# ADCs.net
KiCad netlist of a schematic drawn in Altium Designer
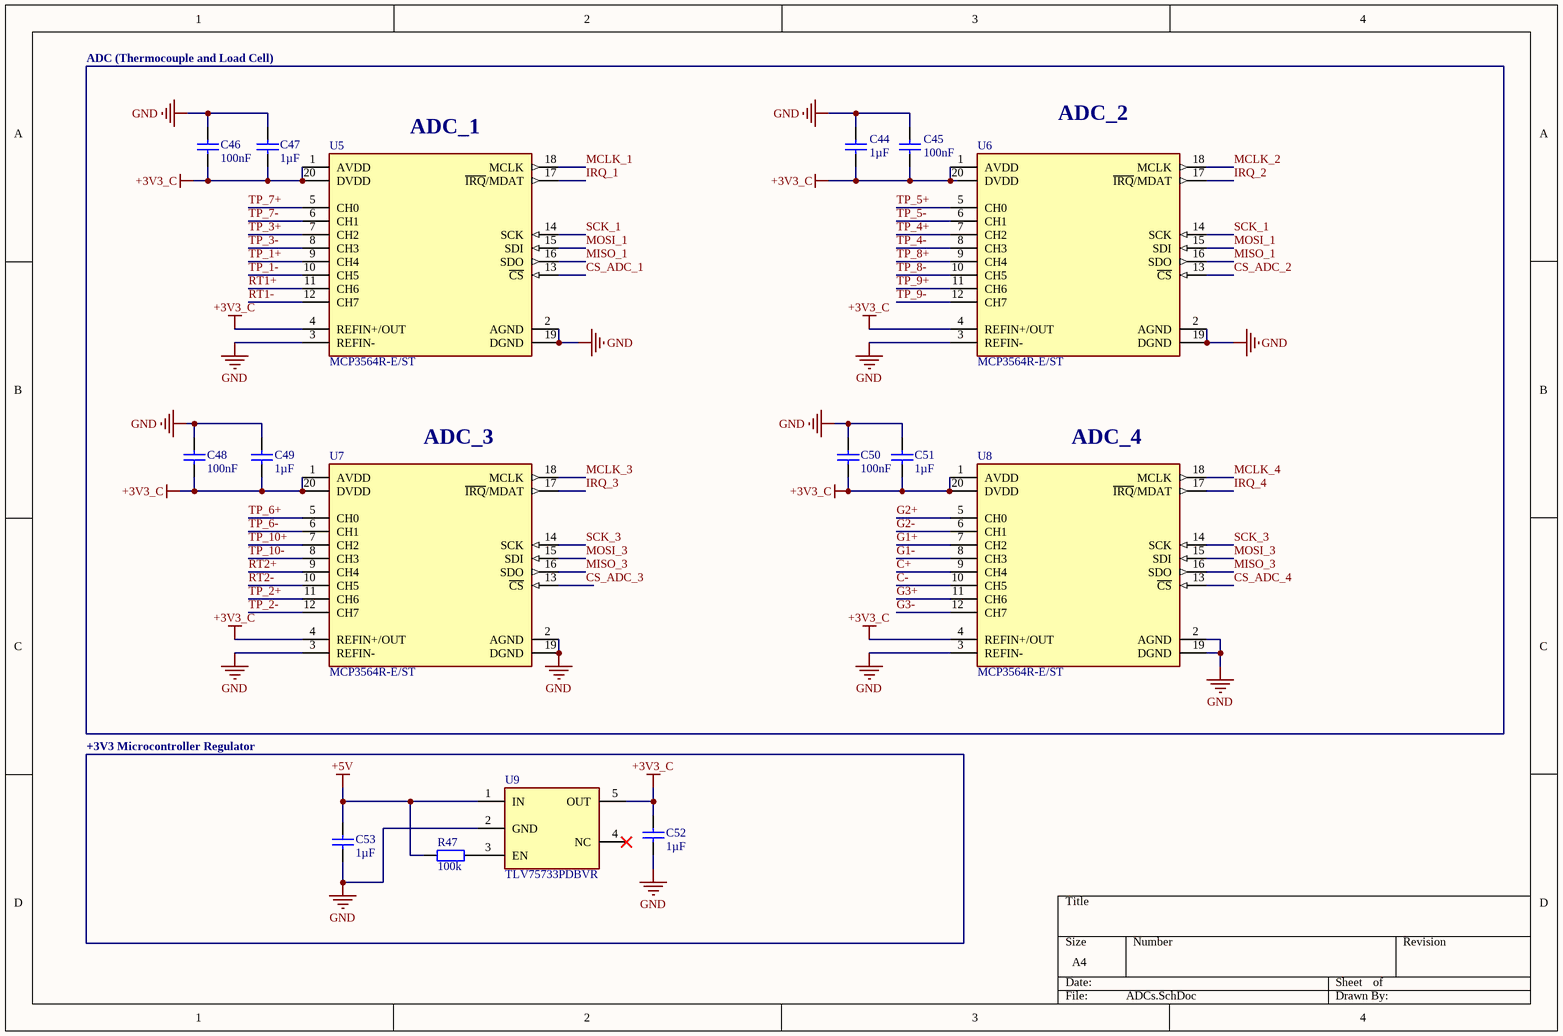
[diagram p0: ADCs.SchDoc]

(export (version "E")
  (design (tool "Eeschema 10.0.6"))
  (components
    (comp (ref "C44")
      (value "1µF")
      (footprint "WCAP-CSGP_0603_L1.6W0.8H0.8_Reflow")
      (description "WCAP-CSGP Multilayer Ceramic Chip Capacitor, General Purpose, size 0603, X7R, 1uF, 16VDC")
      (fields
        (field (name "MANUFACTURER") "Wurth Elektronik")
        (field (name "MANUFACTURER PART NUMBER") "885012206052")
      )
      (libsource (lib "LEEM UPM") (part "885012209047R"))
    )
    (comp (ref "C45")
      (value "100nF")
      (footprint "WCAP-CSGP_0603_L1.6W0.8H0.8_Reflow")
      (description "WCAP-CSGP Multilayer Ceramic Chip Capacitor, General Purpose, size 0603, X7R, 100nF, 25VDC")
      (fields
        (field (name "MANUFACTURER") "Wurth Elektronik")
        (field (name "MANUFACTURER PART NUMBER") "885012206071")
      )
      (libsource (lib "LEEM UPM") (part "885012209047R"))
    )
    (comp (ref "C46")
      (value "100nF")
      (footprint "WCAP-CSGP_0603_L1.6W0.8H0.8_Reflow")
      (description "WCAP-CSGP Multilayer Ceramic Chip Capacitor, General Purpose, size 0603, X7R, 100nF, 25VDC")
      (fields
        (field (name "MANUFACTURER") "Wurth Elektronik")
        (field (name "MANUFACTURER PART NUMBER") "885012206071")
      )
      (libsource (lib "LEEM UPM") (part "885012209047R"))
    )
    (comp (ref "C47")
      (value "1µF")
      (footprint "WCAP-CSGP_0603_L1.6W0.8H0.8_Reflow")
      (description "WCAP-CSGP Multilayer Ceramic Chip Capacitor, General Purpose, size 0603, X7R, 1uF, 16VDC")
      (fields
        (field (name "MANUFACTURER") "Wurth Elektronik")
        (field (name "MANUFACTURER PART NUMBER") "885012206052")
      )
      (libsource (lib "LEEM UPM") (part "885012209047R"))
    )
    (comp (ref "C48")
      (value "100nF")
      (footprint "WCAP-CSGP_0603_L1.6W0.8H0.8_Reflow")
      (description "WCAP-CSGP Multilayer Ceramic Chip Capacitor, General Purpose, size 0603, X7R, 100nF, 25VDC")
      (fields
        (field (name "MANUFACTURER") "Wurth Elektronik")
        (field (name "MANUFACTURER PART NUMBER") "885012206071")
      )
      (libsource (lib "LEEM UPM") (part "885012209047R"))
    )
    (comp (ref "C49")
      (value "1µF")
      (footprint "WCAP-CSGP_0603_L1.6W0.8H0.8_Reflow")
      (description "WCAP-CSGP Multilayer Ceramic Chip Capacitor, General Purpose, size 0603, X7R, 1uF, 16VDC")
      (fields
        (field (name "MANUFACTURER") "Wurth Elektronik")
        (field (name "MANUFACTURER PART NUMBER") "885012206052")
      )
      (libsource (lib "LEEM UPM") (part "885012209047R"))
    )
    (comp (ref "C50")
      (value "100nF")
      (footprint "WCAP-CSGP_0603_L1.6W0.8H0.8_Reflow")
      (description "WCAP-CSGP Multilayer Ceramic Chip Capacitor, General Purpose, size 0603, X7R, 100nF, 25VDC")
      (fields
        (field (name "MANUFACTURER") "Wurth Elektronik")
        (field (name "MANUFACTURER PART NUMBER") "885012206071")
      )
      (libsource (lib "LEEM UPM") (part "885012209047R"))
    )
    (comp (ref "C51")
      (value "1µF")
      (footprint "WCAP-CSGP_0603_L1.6W0.8H0.8_Reflow")
      (description "WCAP-CSGP Multilayer Ceramic Chip Capacitor, General Purpose, size 0603, X7R, 1uF, 16VDC")
      (fields
        (field (name "MANUFACTURER") "Wurth Elektronik")
        (field (name "MANUFACTURER PART NUMBER") "885012206052")
      )
      (libsource (lib "LEEM UPM") (part "885012209047R"))
    )
    (comp (ref "C52")
      (value "1µF")
      (footprint "WCAP-CSGP_0603_L1.6W0.8H0.8_Reflow")
      (description "WCAP-CSGP Multilayer Ceramic Chip Capacitor, General Purpose, size 0603, X7R, 1uF, 16VDC")
      (fields
        (field (name "MANUFACTURER") "Wurth Elektronik")
        (field (name "MANUFACTURER PART NUMBER") "885012206052")
      )
      (libsource (lib "LEEM UPM") (part "885012209047R"))
    )
    (comp (ref "C53")
      (value "1µF")
      (footprint "WCAP-CSGP_0603_L1.6W0.8H0.8_Reflow")
      (description "WCAP-CSGP Multilayer Ceramic Chip Capacitor, General Purpose, size 0603, X7R, 1uF, 16VDC")
      (fields
        (field (name "MANUFACTURER") "Wurth Elektronik")
        (field (name "MANUFACTURER PART NUMBER") "885012206052")
      )
      (libsource (lib "LEEM UPM") (part "885012209047R"))
    )
    (comp (ref "R47")
      (value "100k")
      (footprint "WRIS-RSKS_0603_Reflow")
      (description "WRIS-RSKS Thick Film Resistor, size 0603, 100000Ohm, 100mW")
      (fields
        (field (name "MANUFACTURER PART NUMBER") "560112116004")
        (field (name "MANUFACTURER") "Wurth Elektronik")
      )
      (libsource (lib "LEEM UPM") (part "560112140010"))
    )
    (comp (ref "U5")
      (value "MCP3564R-E/ST")
      (footprint "FP-C04-088-MFG")
      (description "ADC, Delta-Sigma, 24-Bit, 1 Func, 8 Channel, Serial Access, PDSO20")
      (libsource (lib "LEEM UPM") (part "0ac5b573d1d2d90c3815fbc455c1358"))
    )
    (comp (ref "U6")
      (value "MCP3564R-E/ST")
      (footprint "FP-C04-088-MFG")
      (description "ADC, Delta-Sigma, 24-Bit, 1 Func, 8 Channel, Serial Access, PDSO20")
      (libsource (lib "LEEM UPM") (part "0ac5b573d1d2d90c3815fbc455c1358"))
    )
    (comp (ref "U7")
      (value "MCP3564R-E/ST")
      (footprint "FP-C04-088-MFG")
      (description "ADC, Delta-Sigma, 24-Bit, 1 Func, 8 Channel, Serial Access, PDSO20")
      (libsource (lib "LEEM UPM") (part "0ac5b573d1d2d90c3815fbc455c1358"))
    )
    (comp (ref "U8")
      (value "MCP3564R-E/ST")
      (footprint "FP-C04-088-MFG")
      (description "ADC, Delta-Sigma, 24-Bit, 1 Func, 8 Channel, Serial Access, PDSO20")
      (libsource (lib "LEEM UPM") (part "0ac5b573d1d2d90c3815fbc455c1358"))
    )
    (comp (ref "U9")
      (value "TLV75733PDBVR")
      (footprint "SOT95P280X145-5N")
      (description "LDO Voltage Regulators 1A Low-IQ Small-Size Low-Dropout (LDO) Regulator 5-SOT-23 -40 to 125")
      (fields (field (name "MANUFACTURER") "Texas Instruments"))
      (libsource (lib "LEEM UPM") (part "TLV75733PDBVR"))
    )
  )
  (nets
    (net (code "1") (name "+3V3_C") (class "Default")
      (node (ref "C44") (pin "2") (pinfunction "2_2") (pintype "passive"))
      (node (ref "C45") (pin "1") (pinfunction "1_1") (pintype "passive"))
      (node (ref "C46") (pin "2") (pinfunction "2_2") (pintype "passive"))
      (node (ref "C47") (pin "1") (pinfunction "1_1") (pintype "passive"))
      (node (ref "C48") (pin "2") (pinfunction "2_2") (pintype "passive"))
      (node (ref "C49") (pin "1") (pinfunction "1_1") (pintype "passive"))
      (node (ref "C50") (pin "2") (pinfunction "2_2") (pintype "passive"))
      (node (ref "C51") (pin "1") (pinfunction "1_1") (pintype "passive"))
      (node (ref "C52") (pin "2") (pinfunction "2_2") (pintype "passive"))
      (node (ref "U5") (pin "1") (pinfunction "AVDD_1") (pintype "power_in"))
      (node (ref "U5") (pin "20") (pinfunction "DVDD_20") (pintype "power_in"))
      (node (ref "U5") (pin "4") (pinfunction "REFIN+/OUT_4") (pintype "passive"))
      (node (ref "U6") (pin "1") (pinfunction "AVDD_1") (pintype "power_in"))
      (node (ref "U6") (pin "20") (pinfunction "DVDD_20") (pintype "power_in"))
      (node (ref "U6") (pin "4") (pinfunction "REFIN+/OUT_4") (pintype "passive"))
      (node (ref "U7") (pin "1") (pinfunction "AVDD_1") (pintype "power_in"))
      (node (ref "U7") (pin "20") (pinfunction "DVDD_20") (pintype "power_in"))
      (node (ref "U7") (pin "4") (pinfunction "REFIN+/OUT_4") (pintype "passive"))
      (node (ref "U8") (pin "1") (pinfunction "AVDD_1") (pintype "power_in"))
      (node (ref "U8") (pin "20") (pinfunction "DVDD_20") (pintype "power_in"))
      (node (ref "U8") (pin "4") (pinfunction "REFIN+/OUT_4") (pintype "passive"))
      (node (ref "U9") (pin "5") (pinfunction "OUT_5") (pintype "passive"))
    )
    (net (code "2") (name "+5V") (class "Default")
      (node (ref "C53") (pin "2") (pinfunction "2_2") (pintype "passive"))
      (node (ref "R47") (pin "1") (pinfunction "1_1") (pintype "passive"))
      (node (ref "U9") (pin "1") (pinfunction "IN_1") (pintype "power_in"))
    )
    (net (code "3") (name "/C+") (class "Default")
      (node (ref "U8") (pin "9") (pinfunction "CH4_9") (pintype "passive"))
    )
    (net (code "4") (name "/C-") (class "Default")
      (node (ref "U8") (pin "10") (pinfunction "CH5_10") (pintype "passive"))
    )
    (net (code "5") (name "/CS_ADC_1") (class "Default")
      (node (ref "U5") (pin "13") (pinfunction "~{CS}_13") (pintype "input"))
    )
    (net (code "6") (name "/CS_ADC_2") (class "Default")
      (node (ref "U6") (pin "13") (pinfunction "~{CS}_13") (pintype "input"))
    )
    (net (code "7") (name "/CS_ADC_3") (class "Default")
      (node (ref "U7") (pin "13") (pinfunction "~{CS}_13") (pintype "input"))
    )
    (net (code "8") (name "/CS_ADC_4") (class "Default")
      (node (ref "U8") (pin "13") (pinfunction "~{CS}_13") (pintype "input"))
    )
    (net (code "9") (name "/G1+") (class "Default")
      (node (ref "U8") (pin "7") (pinfunction "CH2_7") (pintype "passive"))
    )
    (net (code "10") (name "/G1-") (class "Default")
      (node (ref "U8") (pin "8") (pinfunction "CH3_8") (pintype "passive"))
    )
    (net (code "11") (name "/G2+") (class "Default")
      (node (ref "U8") (pin "5") (pinfunction "CH0_5") (pintype "passive"))
    )
    (net (code "12") (name "/G2-") (class "Default")
      (node (ref "U8") (pin "6") (pinfunction "CH1_6") (pintype "passive"))
    )
    (net (code "13") (name "/G3+") (class "Default")
      (node (ref "U8") (pin "11") (pinfunction "CH6_11") (pintype "passive"))
    )
    (net (code "14") (name "/G3-") (class "Default")
      (node (ref "U8") (pin "12") (pinfunction "CH7_12") (pintype "passive"))
    )
    (net (code "15") (name "/IRQ_1") (class "Default")
      (node (ref "U5") (pin "17") (pinfunction "~{IRQ}/MDAT_17") (pintype "output"))
    )
    (net (code "16") (name "/IRQ_2") (class "Default")
      (node (ref "U6") (pin "17") (pinfunction "~{IRQ}/MDAT_17") (pintype "output"))
    )
    (net (code "17") (name "/IRQ_3") (class "Default")
      (node (ref "U7") (pin "17") (pinfunction "~{IRQ}/MDAT_17") (pintype "output"))
    )
    (net (code "18") (name "/IRQ_4") (class "Default")
      (node (ref "U8") (pin "17") (pinfunction "~{IRQ}/MDAT_17") (pintype "output"))
    )
    (net (code "19") (name "/MCLK_1") (class "Default")
      (node (ref "U5") (pin "18") (pinfunction "MCLK_18") (pintype "output"))
    )
    (net (code "20") (name "/MCLK_2") (class "Default")
      (node (ref "U6") (pin "18") (pinfunction "MCLK_18") (pintype "output"))
    )
    (net (code "21") (name "/MCLK_3") (class "Default")
      (node (ref "U7") (pin "18") (pinfunction "MCLK_18") (pintype "output"))
    )
    (net (code "22") (name "/MCLK_4") (class "Default")
      (node (ref "U8") (pin "18") (pinfunction "MCLK_18") (pintype "output"))
    )
    (net (code "23") (name "/MISO_1") (class "Default")
      (node (ref "U5") (pin "16") (pinfunction "SDO_16") (pintype "output"))
      (node (ref "U6") (pin "16") (pinfunction "SDO_16") (pintype "output"))
    )
    (net (code "24") (name "/MISO_3") (class "Default")
      (node (ref "U7") (pin "16") (pinfunction "SDO_16") (pintype "output"))
      (node (ref "U8") (pin "16") (pinfunction "SDO_16") (pintype "output"))
    )
    (net (code "25") (name "/MOSI_1") (class "Default")
      (node (ref "U5") (pin "15") (pinfunction "SDI_15") (pintype "input"))
      (node (ref "U6") (pin "15") (pinfunction "SDI_15") (pintype "input"))
    )
    (net (code "26") (name "/MOSI_3") (class "Default")
      (node (ref "U7") (pin "15") (pinfunction "SDI_15") (pintype "input"))
      (node (ref "U8") (pin "15") (pinfunction "SDI_15") (pintype "input"))
    )
    (net (code "27") (name "/RT1+") (class "Default")
      (node (ref "U5") (pin "11") (pinfunction "CH6_11") (pintype "passive"))
    )
    (net (code "28") (name "/RT1-") (class "Default")
      (node (ref "U5") (pin "12") (pinfunction "CH7_12") (pintype "passive"))
    )
    (net (code "29") (name "/RT2+") (class "Default")
      (node (ref "U7") (pin "9") (pinfunction "CH4_9") (pintype "passive"))
    )
    (net (code "30") (name "/RT2-") (class "Default")
      (node (ref "U7") (pin "10") (pinfunction "CH5_10") (pintype "passive"))
    )
    (net (code "31") (name "/SCK_1") (class "Default")
      (node (ref "U5") (pin "14") (pinfunction "SCK_14") (pintype "input"))
      (node (ref "U6") (pin "14") (pinfunction "SCK_14") (pintype "input"))
    )
    (net (code "32") (name "/SCK_3") (class "Default")
      (node (ref "U7") (pin "14") (pinfunction "SCK_14") (pintype "input"))
      (node (ref "U8") (pin "14") (pinfunction "SCK_14") (pintype "input"))
    )
    (net (code "33") (name "/TP_1+") (class "Default")
      (node (ref "U5") (pin "9") (pinfunction "CH4_9") (pintype "passive"))
    )
    (net (code "34") (name "/TP_1-") (class "Default")
      (node (ref "U5") (pin "10") (pinfunction "CH5_10") (pintype "passive"))
    )
    (net (code "35") (name "/TP_2+") (class "Default")
      (node (ref "U7") (pin "11") (pinfunction "CH6_11") (pintype "passive"))
    )
    (net (code "36") (name "/TP_2-") (class "Default")
      (node (ref "U7") (pin "12") (pinfunction "CH7_12") (pintype "passive"))
    )
    (net (code "37") (name "/TP_3+") (class "Default")
      (node (ref "U5") (pin "7") (pinfunction "CH2_7") (pintype "passive"))
    )
    (net (code "38") (name "/TP_3-") (class "Default")
      (node (ref "U5") (pin "8") (pinfunction "CH3_8") (pintype "passive"))
    )
    (net (code "39") (name "/TP_4+") (class "Default")
      (node (ref "U6") (pin "7") (pinfunction "CH2_7") (pintype "passive"))
    )
    (net (code "40") (name "/TP_4-") (class "Default")
      (node (ref "U6") (pin "8") (pinfunction "CH3_8") (pintype "passive"))
    )
    (net (code "41") (name "/TP_5+") (class "Default")
      (node (ref "U6") (pin "5") (pinfunction "CH0_5") (pintype "passive"))
    )
    (net (code "42") (name "/TP_5-") (class "Default")
      (node (ref "U6") (pin "6") (pinfunction "CH1_6") (pintype "passive"))
    )
    (net (code "43") (name "/TP_6+") (class "Default")
      (node (ref "U7") (pin "5") (pinfunction "CH0_5") (pintype "passive"))
    )
    (net (code "44") (name "/TP_6-") (class "Default")
      (node (ref "U7") (pin "6") (pinfunction "CH1_6") (pintype "passive"))
    )
    (net (code "45") (name "/TP_7+") (class "Default")
      (node (ref "U5") (pin "5") (pinfunction "CH0_5") (pintype "passive"))
    )
    (net (code "46") (name "/TP_7-") (class "Default")
      (node (ref "U5") (pin "6") (pinfunction "CH1_6") (pintype "passive"))
    )
    (net (code "47") (name "/TP_8+") (class "Default")
      (node (ref "U6") (pin "9") (pinfunction "CH4_9") (pintype "passive"))
    )
    (net (code "48") (name "/TP_8-") (class "Default")
      (node (ref "U6") (pin "10") (pinfunction "CH5_10") (pintype "passive"))
    )
    (net (code "49") (name "/TP_9+") (class "Default")
      (node (ref "U6") (pin "11") (pinfunction "CH6_11") (pintype "passive"))
    )
    (net (code "50") (name "/TP_9-") (class "Default")
      (node (ref "U6") (pin "12") (pinfunction "CH7_12") (pintype "passive"))
    )
    (net (code "51") (name "/TP_10+") (class "Default")
      (node (ref "U7") (pin "7") (pinfunction "CH2_7") (pintype "passive"))
    )
    (net (code "52") (name "/TP_10-") (class "Default")
      (node (ref "U7") (pin "8") (pinfunction "CH3_8") (pintype "passive"))
    )
    (net (code "53") (name "GND") (class "Default")
      (node (ref "C44") (pin "1") (pinfunction "1_1") (pintype "passive"))
      (node (ref "C45") (pin "2") (pinfunction "2_2") (pintype "passive"))
      (node (ref "C46") (pin "1") (pinfunction "1_1") (pintype "passive"))
      (node (ref "C47") (pin "2") (pinfunction "2_2") (pintype "passive"))
      (node (ref "C48") (pin "1") (pinfunction "1_1") (pintype "passive"))
      (node (ref "C49") (pin "2") (pinfunction "2_2") (pintype "passive"))
      (node (ref "C50") (pin "1") (pinfunction "1_1") (pintype "passive"))
      (node (ref "C51") (pin "2") (pinfunction "2_2") (pintype "passive"))
      (node (ref "C52") (pin "1") (pinfunction "1_1") (pintype "passive"))
      (node (ref "C53") (pin "1") (pinfunction "1_1") (pintype "passive"))
      (node (ref "U5") (pin "19") (pinfunction "DGND_19") (pintype "power_in"))
      (node (ref "U5") (pin "2") (pinfunction "AGND_2") (pintype "power_in"))
      (node (ref "U5") (pin "3") (pinfunction "REFIN-_3") (pintype "passive"))
      (node (ref "U6") (pin "19") (pinfunction "DGND_19") (pintype "power_in"))
      (node (ref "U6") (pin "2") (pinfunction "AGND_2") (pintype "power_in"))
      (node (ref "U6") (pin "3") (pinfunction "REFIN-_3") (pintype "passive"))
      (node (ref "U7") (pin "19") (pinfunction "DGND_19") (pintype "power_in"))
      (node (ref "U7") (pin "2") (pinfunction "AGND_2") (pintype "power_in"))
      (node (ref "U7") (pin "3") (pinfunction "REFIN-_3") (pintype "passive"))
      (node (ref "U8") (pin "19") (pinfunction "DGND_19") (pintype "power_in"))
      (node (ref "U8") (pin "2") (pinfunction "AGND_2") (pintype "power_in"))
      (node (ref "U8") (pin "3") (pinfunction "REFIN-_3") (pintype "passive"))
      (node (ref "U9") (pin "2") (pinfunction "GND_2") (pintype "passive"))
    )
    (net (code "54") (name "Net-(U9-EN)") (class "Default")
      (node (ref "R47") (pin "2") (pinfunction "2_2") (pintype "passive"))
      (node (ref "U9") (pin "3") (pinfunction "EN_3") (pintype "passive"))
    )
    (net (code "55") (name "unconnected-(U9-NC-Pad4)") (class "Default")
      (node (ref "U9") (pin "4") (pinfunction "NC_4") (pintype "passive+no_connect"))
    )
  )
)
